# 16_-_POWERS_5V_3V3.net
KiCad netlist of a schematic drawn in Altium Designer
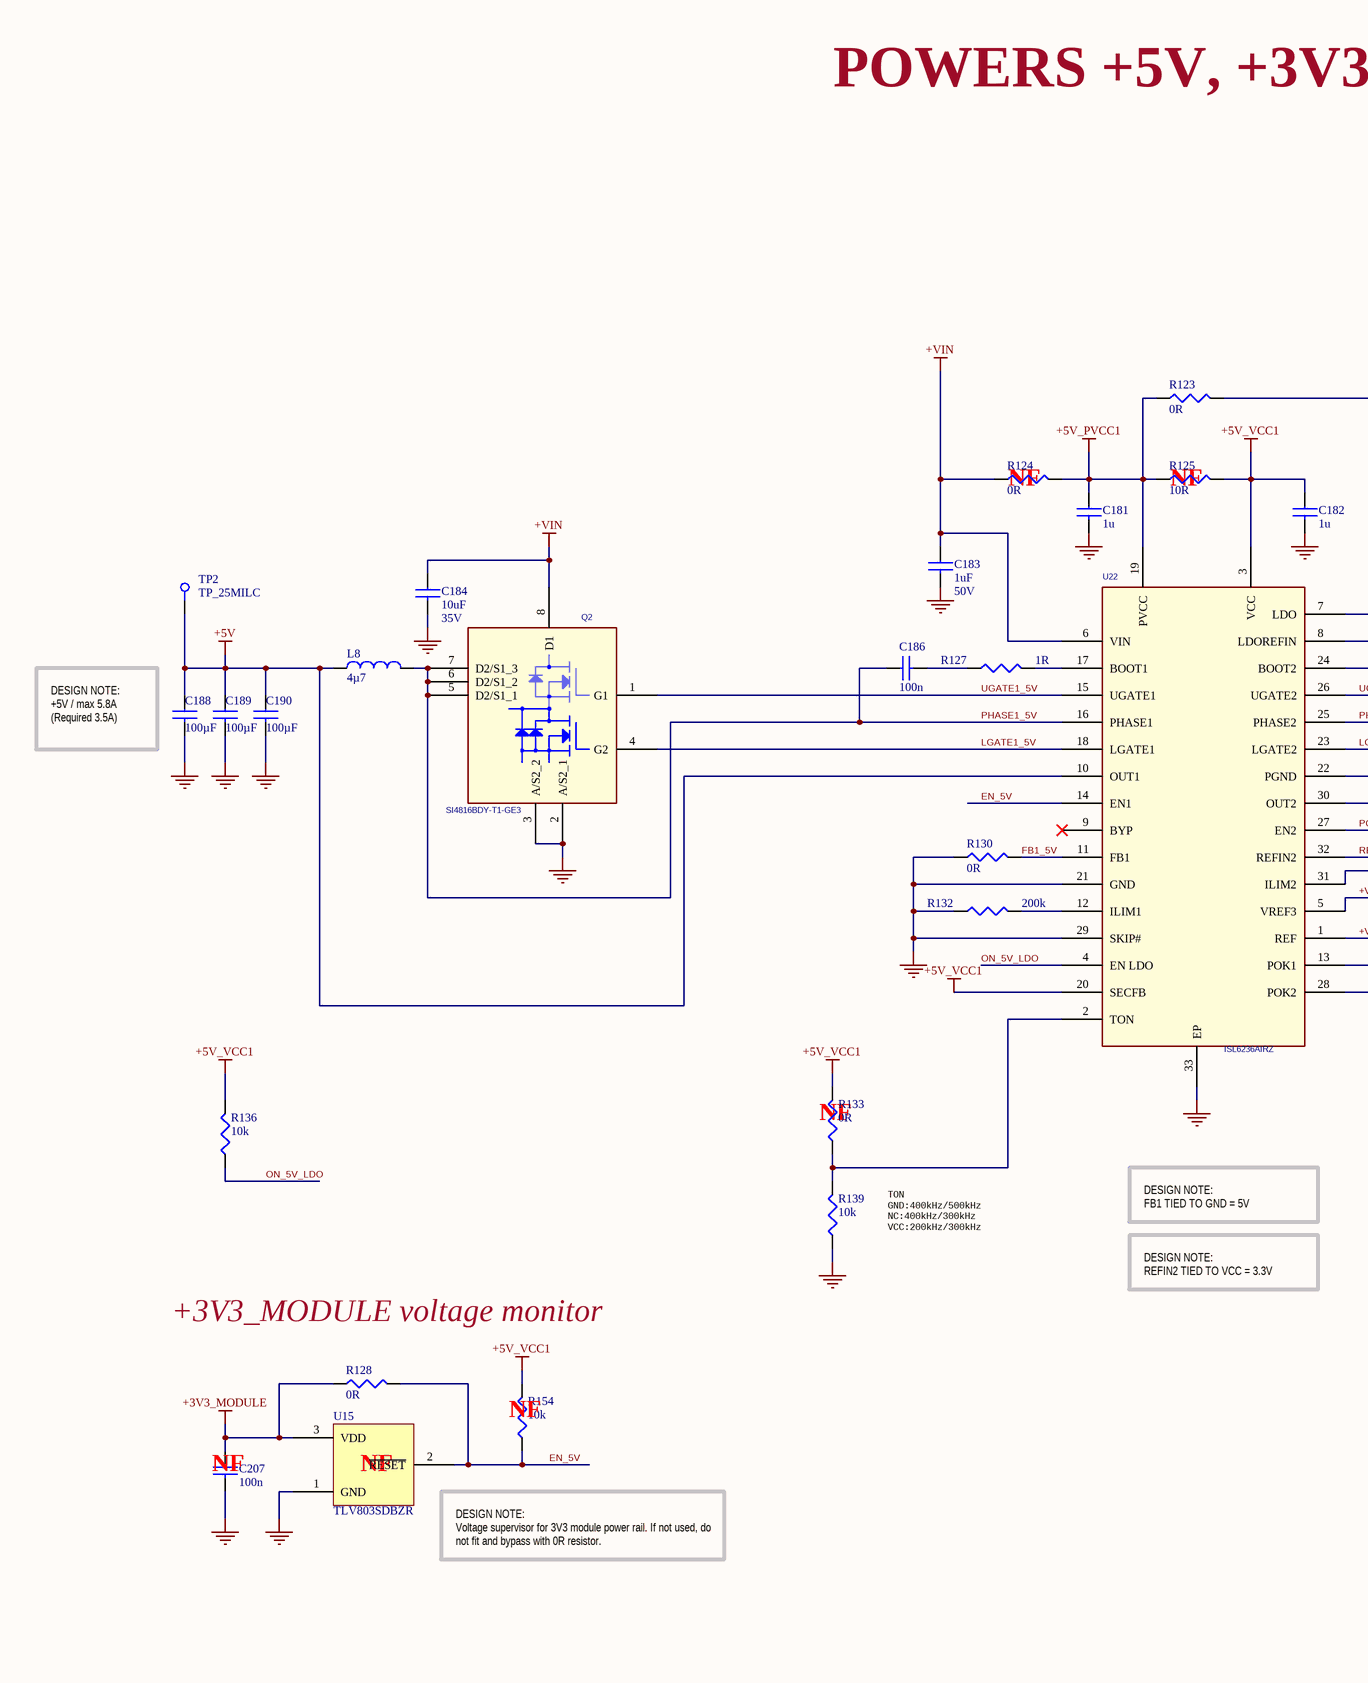
[diagram p0: [16] - POWERS 5V, 3V3.SchDoc, left]
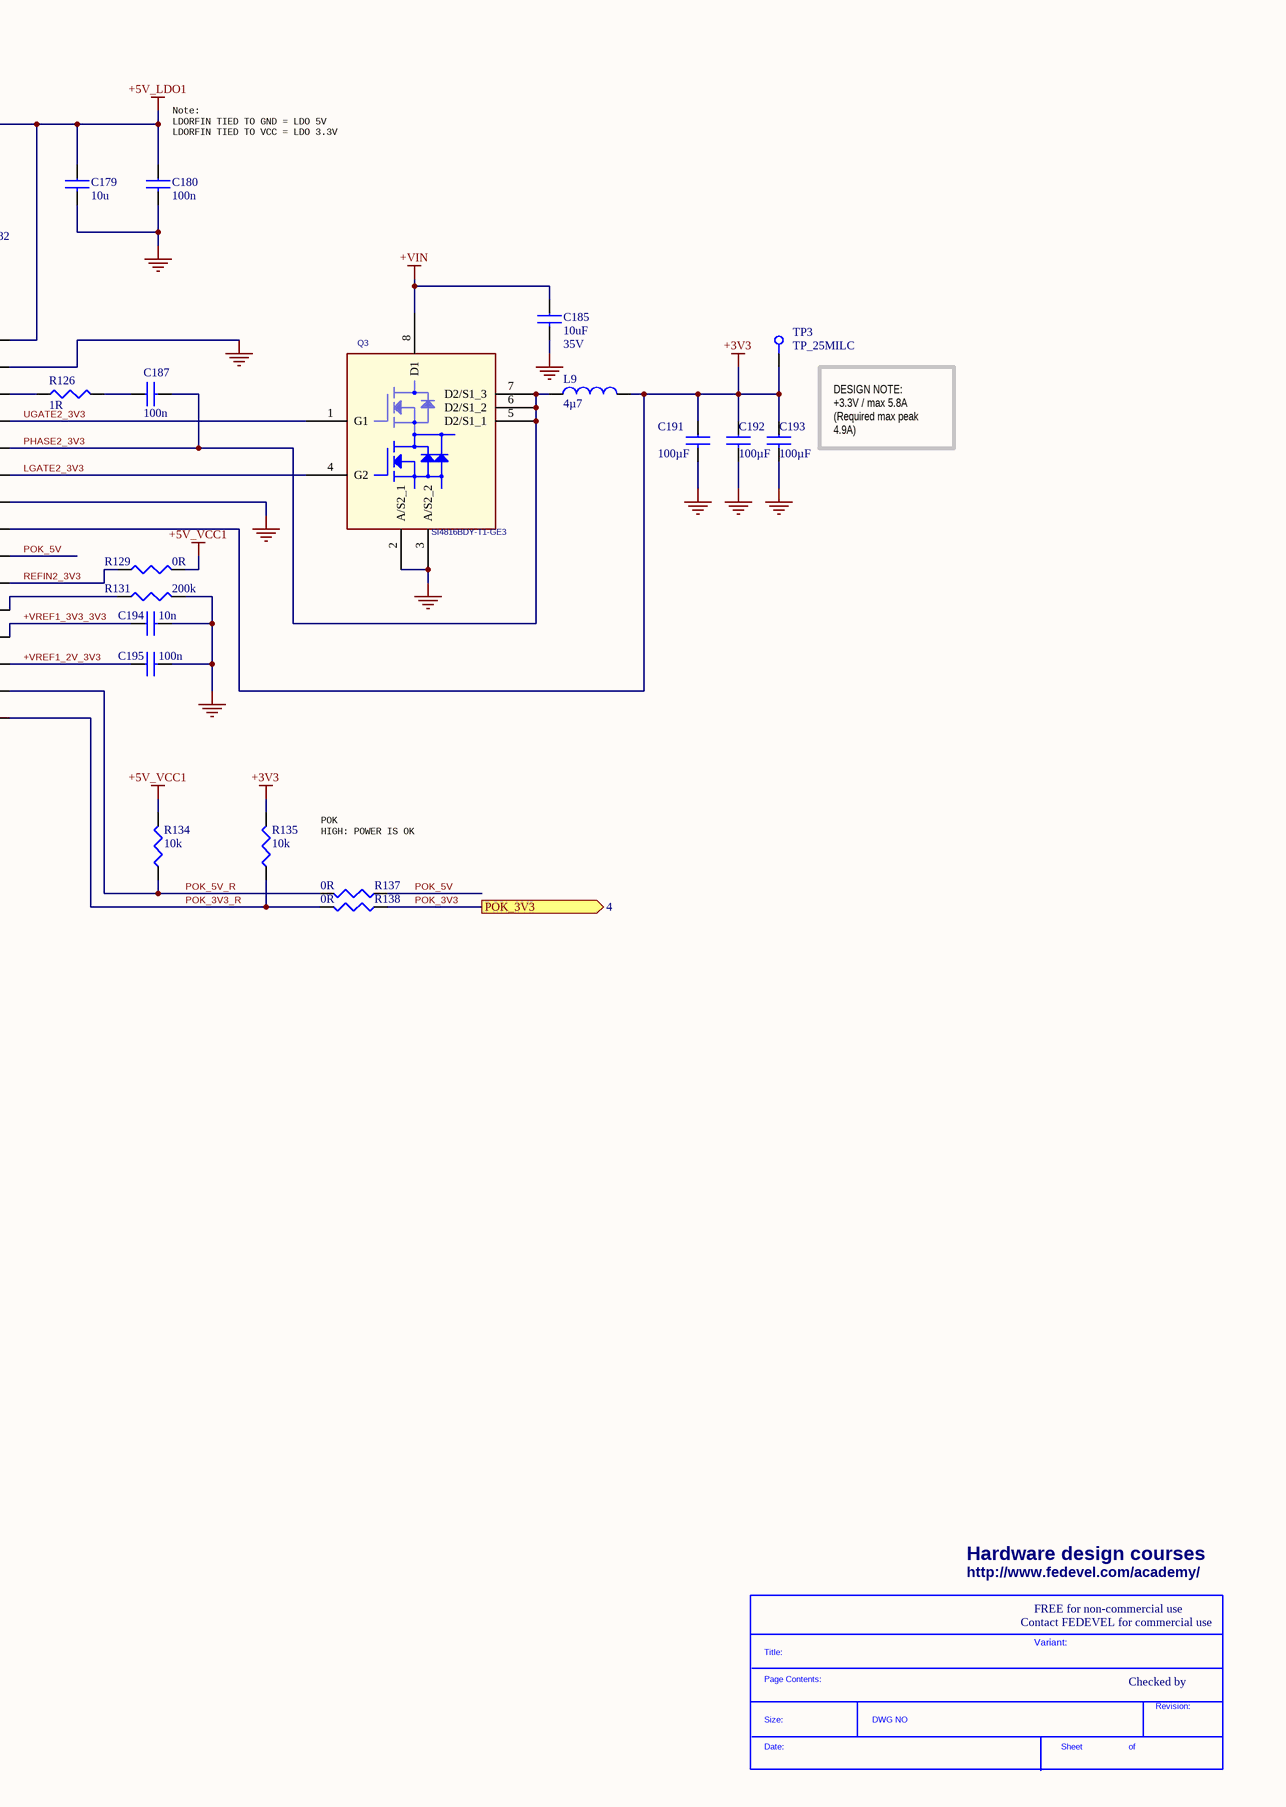
[diagram p1: [16] - POWERS 5V, 3V3.SchDoc, right]

(export (version "E")
  (design (tool "Eeschema 10.0.6"))
  (components
    (comp (ref "C179")
      (value "10u")
      (footprint "C0603")
      (description "CAP CER 10UF 6.3V X5R 20% 0603")
      (fields
        (field (name "MANUFACTURER") "TDK Corporation")
        (field (name "MANUFACTURER PART NUMBER") "C1608X5R0J106M")
      )
      (libsource (lib "Integrated_Library_RF_FEB_2012") (part "C1608X5R0J106M"))
    )
    (comp (ref "C180")
      (value "100n")
      (footprint "C0402")
      (description "CAP CER .10UF 50V X5R 10% 0402")
      (fields
        (field (name "MANUFACTURER") "TDK Corporation")
        (field (name "MANUFACTURER PART NUMBER") "C1005X5R1H104K")
      )
      (libsource (lib "Integrated_Library_RF_FEB_2012") (part "C1005X5R1H104K"))
    )
    (comp (ref "C181")
      (value "1u")
      (footprint "C0402")
      (description "CAP CER 1.0UF 16V X5R 0402")
      (fields
        (field (name "MANUFACTURER") "TDK Corporation")
        (field (name "MANUFACTURER PART NUMBER") "C1005X5R1C105K")
      )
      (libsource (lib "Integrated_Library_RF_FEB_2012") (part "C1005X5R1C105K"))
    )
    (comp (ref "C182")
      (value "1u")
      (footprint "C0402")
      (description "CAP CER 1.0UF 16V X5R 0402")
      (fields
        (field (name "MANUFACTURER") "TDK Corporation")
        (field (name "MANUFACTURER PART NUMBER") "C1005X5R1C105K")
      )
      (libsource (lib "Integrated_Library_RF_FEB_2012") (part "C1005X5R1C105K"))
    )
    (comp (ref "C183")
      (value "1uF")
      (footprint "C0805")
      (description "CAP CER 1UF 50V X7R 0805")
      (fields
        (field (name "MANUFACTURER") "Murata Electronics North America")
        (field (name "MANUFACTURER PART NUMBER") "GRM21BR71H105KA12L")
        (field (name "VOLTAGE - RATED") "50V")
      )
      (libsource (lib "Integrated_Library_RF_FEB_2012") (part "GRM21BR71H105KA12L"))
    )
    (comp (ref "C184")
      (value "10uF")
      (footprint "C1206")
      (description "CAP CER 10UF 35V X5R 1206")
      (fields
        (field (name "MANUFACTURER") "Murata Electronics North America")
        (field (name "MANUFACTURER PART NUMBER") "GRM31CR6YA106KA12L")
        (field (name "VOLTAGE - RATED") "35V")
      )
      (libsource (lib "Integrated_Library_RF_FEB_2012") (part "GRM31CR6YA106KA12L"))
    )
    (comp (ref "C185")
      (value "10uF")
      (footprint "C1206")
      (description "CAP CER 10UF 35V X5R 1206")
      (fields
        (field (name "MANUFACTURER") "Murata Electronics North America")
        (field (name "MANUFACTURER PART NUMBER") "GRM31CR6YA106KA12L")
        (field (name "VOLTAGE - RATED") "35V")
      )
      (libsource (lib "Integrated_Library_RF_FEB_2012") (part "GRM31CR6YA106KA12L"))
    )
    (comp (ref "C186")
      (value "100n")
      (footprint "C0402")
      (description "CAP CER .10UF 50V X5R 10% 0402")
      (fields
        (field (name "MANUFACTURER") "TDK Corporation")
        (field (name "MANUFACTURER PART NUMBER") "C1005X5R1H104K")
      )
      (libsource (lib "Integrated_Library_RF_FEB_2012") (part "C1005X5R1H104K"))
    )
    (comp (ref "C187")
      (value "100n")
      (footprint "C0402")
      (description "CAP CER .10UF 50V X5R 10% 0402")
      (fields
        (field (name "MANUFACTURER") "TDK Corporation")
        (field (name "MANUFACTURER PART NUMBER") "C1005X5R1H104K")
      )
      (libsource (lib "Integrated_Library_RF_FEB_2012") (part "C1005X5R1H104K"))
    )
    (comp (ref "C188")
      (value "100µF")
      (footprint "C1206")
      (description "CAP CER 100UF 10V X5R 20% 1206")
      (fields
        (field (name "MANUFACTURER") "TDK Corporation")
        (field (name "MANUFACTURER PART NUMBER") "C3216X5R1A107M")
      )
      (libsource (lib "Integrated_Library_RF_FEB_2012") (part "C3216X5R1A107M"))
    )
    (comp (ref "C189")
      (value "100µF")
      (footprint "C1206")
      (description "CAP CER 100UF 10V X5R 20% 1206")
      (fields
        (field (name "MANUFACTURER") "TDK Corporation")
        (field (name "MANUFACTURER PART NUMBER") "C3216X5R1A107M")
      )
      (libsource (lib "Integrated_Library_RF_FEB_2012") (part "C3216X5R1A107M"))
    )
    (comp (ref "C190")
      (value "100µF")
      (footprint "C1206")
      (description "CAP CER 100UF 10V X5R 20% 1206")
      (fields
        (field (name "MANUFACTURER") "TDK Corporation")
        (field (name "MANUFACTURER PART NUMBER") "C3216X5R1A107M")
      )
      (libsource (lib "Integrated_Library_RF_FEB_2012") (part "C3216X5R1A107M"))
    )
    (comp (ref "C191")
      (value "100µF")
      (footprint "C1206")
      (description "CAP CER 100UF 10V X5R 20% 1206")
      (fields
        (field (name "MANUFACTURER") "TDK Corporation")
        (field (name "MANUFACTURER PART NUMBER") "C3216X5R1A107M")
      )
      (libsource (lib "Integrated_Library_RF_FEB_2012") (part "C3216X5R1A107M"))
    )
    (comp (ref "C192")
      (value "100µF")
      (footprint "C1206")
      (description "CAP CER 100UF 10V X5R 20% 1206")
      (fields
        (field (name "MANUFACTURER") "TDK Corporation")
        (field (name "MANUFACTURER PART NUMBER") "C3216X5R1A107M")
      )
      (libsource (lib "Integrated_Library_RF_FEB_2012") (part "C3216X5R1A107M"))
    )
    (comp (ref "C193")
      (value "100µF")
      (footprint "C1206")
      (description "CAP CER 100UF 10V X5R 20% 1206")
      (fields
        (field (name "MANUFACTURER") "TDK Corporation")
        (field (name "MANUFACTURER PART NUMBER") "C3216X5R1A107M")
      )
      (libsource (lib "Integrated_Library_RF_FEB_2012") (part "C3216X5R1A107M"))
    )
    (comp (ref "C194")
      (value "10n")
      (footprint "C0402")
      (description "CAP CER 10000PF 16V X7R 10% 0402")
      (fields
        (field (name "MANUFACTURER") "TDK Corporation")
        (field (name "MANUFACTURER PART NUMBER") "C1005X7R1C103K")
      )
      (libsource (lib "Integrated_Library_RF_FEB_2012") (part "C1005X7R1C103K"))
    )
    (comp (ref "C195")
      (value "100n")
      (footprint "C0402")
      (description "CAP CER .10UF 50V X5R 10% 0402")
      (fields
        (field (name "MANUFACTURER") "TDK Corporation")
        (field (name "MANUFACTURER PART NUMBER") "C1005X5R1H104K")
      )
      (libsource (lib "Integrated_Library_RF_FEB_2012") (part "C1005X5R1H104K"))
    )
    (comp (ref "C207")
      (value "100n")
      (footprint "C0402")
      (description "CAP CER .10UF 50V X5R 10% 0402")
      (fields
        (field (name "MANUFACTURER") "TDK Corporation")
        (field (name "MANUFACTURER PART NUMBER") "C1005X5R1H104K")
      )
      (libsource (lib "Integrated_Library_RF_FEB_2012") (part "C1005X5R1H104K"))
    )
    (comp (ref "L8")
      (value "4µ7")
      (footprint "IHLP_255MILx270MIL")
      (description "INDUCTOR POWER 4.7UH 5.5A SMD")
      (fields
        (field (name "MANUFACTURER") "Vishay/Dale")
        (field (name "MANUFACTURER PART NUMBER") "IHLP2525CZER4R7M01")
      )
      (libsource (lib "Integrated_Library_RF_FEB_2012") (part "IHLP2525CZER4R7M01"))
    )
    (comp (ref "L9")
      (value "4µ7")
      (footprint "IHLP_255MILx270MIL")
      (description "INDUCTOR POWER 4.7UH 5.5A SMD")
      (fields
        (field (name "MANUFACTURER") "Vishay/Dale")
        (field (name "MANUFACTURER PART NUMBER") "IHLP2525CZER4R7M01")
      )
      (libsource (lib "Integrated_Library_RF_FEB_2012") (part "IHLP2525CZER4R7M01"))
    )
    (comp (ref "Q2")
      (value "SI4816BDY-T1-GE3")
      (footprint "8_SOIC_3.9MM")
      (description "MOSFET DL N-CH 30V 6.8A 8-SOIC")
      (fields (field (name "MANUFACTURER") "Vishay/Siliconix"))
      (libsource (lib "Integrated_Library_RF_FEB_2012") (part "SI4816BDY-T1-GE3"))
    )
    (comp (ref "Q3")
      (value "SI4816BDY-T1-GE3")
      (footprint "8_SOIC_3.9MM")
      (description "MOSFET DL N-CH 30V 6.8A 8-SOIC")
      (fields (field (name "MANUFACTURER") "Vishay/Siliconix"))
      (libsource (lib "Integrated_Library_RF_FEB_2012") (part "SI4816BDY-T1-GE3"))
    )
    (comp (ref "R123")
      (value "0R")
      (footprint "R0402")
      (description "RES 0.0 OHM 1/16W 0402 SMD")
      (fields
        (field (name "MANUFACTURER") "Yageo")
        (field (name "MANUFACTURER PART NUMBER") "RC0402JR-070RL")
      )
      (libsource (lib "Integrated_Library_RF_FEB_2012") (part "RC0402JR-070RL"))
    )
    (comp (ref "R124")
      (value "0R")
      (footprint "R0402")
      (description "RES 0.0 OHM 1/16W 0402 SMD")
      (fields
        (field (name "MANUFACTURER") "Yageo")
        (field (name "MANUFACTURER PART NUMBER") "RC0402JR-070RL")
      )
      (libsource (lib "Integrated_Library_RF_FEB_2012") (part "RC0402JR-070RL"))
    )
    (comp (ref "R125")
      (value "10R")
      (footprint "R0402")
      (description "RES 10.0 OHM 1/16W 1% 0402 SMD")
      (fields
        (field (name "MANUFACTURER") "Yageo")
        (field (name "MANUFACTURER PART NUMBER") "RC0402FR-0710RL")
      )
      (libsource (lib "Integrated_Library_RF_FEB_2012") (part "RC0402FR-0710RL"))
    )
    (comp (ref "R126")
      (value "1R")
      (footprint "R0402")
      (description "RES 1.00 OHM 1/16W 1% 0402 SM")
      (fields
        (field (name "MANUFACTURER") "Yageo")
        (field (name "MANUFACTURER PART NUMBER") "RC0402FR-071RL")
      )
      (libsource (lib "Integrated_Library_RF_FEB_2012") (part "RC0402FR-071RL"))
    )
    (comp (ref "R127")
      (value "1R")
      (footprint "R0402")
      (description "RES 1.00 OHM 1/16W 1% 0402 SM")
      (fields
        (field (name "MANUFACTURER") "Yageo")
        (field (name "MANUFACTURER PART NUMBER") "RC0402FR-071RL")
      )
      (libsource (lib "Integrated_Library_RF_FEB_2012") (part "RC0402FR-071RL"))
    )
    (comp (ref "R128")
      (value "0R")
      (footprint "R0402")
      (description "RES 0.0 OHM 1/16W 0402 SMD")
      (fields
        (field (name "MANUFACTURER") "Yageo")
        (field (name "MANUFACTURER PART NUMBER") "RC0402JR-070RL")
      )
      (libsource (lib "Integrated_Library_RF_FEB_2012") (part "RC0402JR-070RL"))
    )
    (comp (ref "R129")
      (value "0R")
      (footprint "R0402")
      (description "RES 0.0 OHM 1/16W 0402 SMD")
      (fields
        (field (name "MANUFACTURER") "Yageo")
        (field (name "MANUFACTURER PART NUMBER") "RC0402JR-070RL")
      )
      (libsource (lib "Integrated_Library_RF_FEB_2012") (part "RC0402JR-070RL"))
    )
    (comp (ref "R130")
      (value "0R")
      (footprint "R0402")
      (description "RES 0.0 OHM 1/16W 0402 SMD")
      (fields
        (field (name "MANUFACTURER") "Yageo")
        (field (name "MANUFACTURER PART NUMBER") "RC0402JR-070RL")
      )
      (libsource (lib "Integrated_Library_RF_FEB_2012") (part "RC0402JR-070RL"))
    )
    (comp (ref "R131")
      (value "200k")
      (footprint "R0402")
      (description "RES 200K OHM 1/16W 1% 0402 SMD")
      (fields
        (field (name "MANUFACTURER") "Yageo")
        (field (name "MANUFACTURER PART NUMBER") "RC0402FR-07200KL")
      )
      (libsource (lib "Integrated_Library_RF_FEB_2012") (part "RC0402FR-07200KL"))
    )
    (comp (ref "R132")
      (value "200k")
      (footprint "R0402")
      (description "RES 200K OHM 1/16W 1% 0402 SMD")
      (fields
        (field (name "MANUFACTURER") "Yageo")
        (field (name "MANUFACTURER PART NUMBER") "RC0402FR-07200KL")
      )
      (libsource (lib "Integrated_Library_RF_FEB_2012") (part "RC0402FR-07200KL"))
    )
    (comp (ref "R133")
      (value "0R")
      (footprint "R0402")
      (description "RES 0.0 OHM 1/16W 0402 SMD")
      (fields
        (field (name "MANUFACTURER") "Yageo")
        (field (name "MANUFACTURER PART NUMBER") "RC0402JR-070RL")
      )
      (libsource (lib "Integrated_Library_RF_FEB_2012") (part "RC0402JR-070RL"))
    )
    (comp (ref "R134")
      (value "10k")
      (footprint "R0402")
      (description "RES 10.0K OHM 1/16W 1% 0402 SMD")
      (fields
        (field (name "MANUFACTURER") "Yageo")
        (field (name "MANUFACTURER PART NUMBER") "RC0402FR-0710KL")
      )
      (libsource (lib "Integrated_Library_RF_FEB_2012") (part "RC0402FR-0710KL"))
    )
    (comp (ref "R135")
      (value "10k")
      (footprint "R0402")
      (description "RES 10.0K OHM 1/16W 1% 0402 SMD")
      (fields
        (field (name "MANUFACTURER") "Yageo")
        (field (name "MANUFACTURER PART NUMBER") "RC0402FR-0710KL")
      )
      (libsource (lib "Integrated_Library_RF_FEB_2012") (part "RC0402FR-0710KL"))
    )
    (comp (ref "R136")
      (value "10k")
      (footprint "R0402")
      (description "RES 10.0K OHM 1/16W 1% 0402 SMD")
      (fields
        (field (name "MANUFACTURER") "Yageo")
        (field (name "MANUFACTURER PART NUMBER") "RC0402FR-0710KL")
      )
      (libsource (lib "Integrated_Library_RF_FEB_2012") (part "RC0402FR-0710KL"))
    )
    (comp (ref "R137")
      (value "0R")
      (footprint "R0402")
      (description "RES 0.0 OHM 1/16W 0402 SMD")
      (fields
        (field (name "MANUFACTURER") "Yageo")
        (field (name "MANUFACTURER PART NUMBER") "RC0402JR-070RL")
      )
      (libsource (lib "Integrated_Library_RF_FEB_2012") (part "RC0402JR-070RL"))
    )
    (comp (ref "R138")
      (value "0R")
      (footprint "R0402")
      (description "RES 0.0 OHM 1/16W 0402 SMD")
      (fields
        (field (name "MANUFACTURER") "Yageo")
        (field (name "MANUFACTURER PART NUMBER") "RC0402JR-070RL")
      )
      (libsource (lib "Integrated_Library_RF_FEB_2012") (part "RC0402JR-070RL"))
    )
    (comp (ref "R139")
      (value "10k")
      (footprint "R0402")
      (description "RES 10.0K OHM 1/16W 1% 0402 SMD")
      (fields
        (field (name "MANUFACTURER") "Yageo")
        (field (name "MANUFACTURER PART NUMBER") "RC0402FR-0710KL")
      )
      (libsource (lib "Integrated_Library_RF_FEB_2012") (part "RC0402FR-0710KL"))
    )
    (comp (ref "R154")
      (value "10k")
      (footprint "R0402")
      (description "RES 10.0K OHM 1/16W 1% 0402 SMD")
      (fields
        (field (name "MANUFACTURER") "Yageo")
        (field (name "MANUFACTURER PART NUMBER") "RC0402FR-0710KL")
      )
      (libsource (lib "Integrated_Library_RF_FEB_2012") (part "RC0402FR-0710KL"))
    )
    (comp (ref "TP2")
      (value "TP_25MILC")
      (footprint "TP_25C")
      (description "Test Point 25mil")
      (libsource (lib "Integrated_Library_RF_FEB_2012") (part "TP_25MILC"))
    )
    (comp (ref "TP3")
      (value "TP_25MILC")
      (footprint "TP_25C")
      (description "Test Point 25mil")
      (libsource (lib "Integrated_Library_RF_FEB_2012") (part "TP_25MILC"))
    )
    (comp (ref "U15")
      (value "TLV803SDBZR")
      (footprint "DBZ")
      (description "IC VOLT SUPERVISR 2.93V SOT23-3")
      (fields
        (field (name "MANUFACTURER") "Texas Instruments")
        (field (name ".CREATOR") "MM")
        (field (name ".CHECKED PCB") "MM")
        (field (name ".CHECKED SCH") "MM")
      )
      (libsource (lib "Integrated_Library_RF_FEB_2012") (part "TLV803SDBZR"))
    )
    (comp (ref "U22")
      (value "ISL6236AIRZ")
      (footprint "32_VFQFN_EXPOSED_PAD")
      (description "IC MAIN PWR CTRLR QUAD 32-QFN")
      (fields (field (name "MANUFACTURER") "Intersil"))
      (libsource (lib "Integrated_Library_RF_FEB_2012") (part "ISL6236AIRZ"))
    )
  )
  (nets
    (net (code "1") (name "+3V3") (class "Default")
      (node (ref "C191") (pin "1") (pinfunction "1_1") (pintype "passive"))
      (node (ref "C192") (pin "1") (pinfunction "1_1") (pintype "passive"))
      (node (ref "C193") (pin "1") (pinfunction "1_1") (pintype "passive"))
      (node (ref "L9") (pin "2") (pinfunction "2_2") (pintype "passive"))
      (node (ref "R135") (pin "2") (pinfunction "2_2") (pintype "passive"))
      (node (ref "TP3") (pin "1") (pinfunction "1_1") (pintype "passive"))
      (node (ref "U22") (pin "30") (pinfunction "OUT2_30") (pintype "passive"))
    )
    (net (code "2") (name "+3V3_MODULE") (class "Default")
      (node (ref "C207") (pin "1") (pinfunction "1_1") (pintype "passive"))
      (node (ref "R128") (pin "1") (pinfunction "1_1") (pintype "passive"))
      (node (ref "U15") (pin "3") (pinfunction "VDD_3") (pintype "passive"))
    )
    (net (code "3") (name "+5V") (class "Default")
      (node (ref "C188") (pin "1") (pinfunction "1_1") (pintype "passive"))
      (node (ref "C189") (pin "1") (pinfunction "1_1") (pintype "passive"))
      (node (ref "C190") (pin "1") (pinfunction "1_1") (pintype "passive"))
      (node (ref "L8") (pin "1") (pinfunction "1_1") (pintype "passive"))
      (node (ref "TP2") (pin "1") (pinfunction "1_1") (pintype "passive"))
      (node (ref "U22") (pin "10") (pinfunction "OUT1_10") (pintype "passive"))
    )
    (net (code "4") (name "+5V_LDO1") (class "Default")
      (node (ref "C179") (pin "1") (pinfunction "1_1") (pintype "passive"))
      (node (ref "C180") (pin "1") (pinfunction "1_1") (pintype "passive"))
      (node (ref "R123") (pin "2") (pinfunction "2_2") (pintype "passive"))
      (node (ref "U22") (pin "7") (pinfunction "LDO_7") (pintype "passive"))
    )
    (net (code "5") (name "+5V_PVCC1") (class "Default")
      (node (ref "C181") (pin "1") (pinfunction "1_1") (pintype "passive"))
      (node (ref "R123") (pin "1") (pinfunction "1_1") (pintype "passive"))
      (node (ref "R124") (pin "2") (pinfunction "2_2") (pintype "passive"))
      (node (ref "R125") (pin "1") (pinfunction "1_1") (pintype "passive"))
      (node (ref "U22") (pin "19") (pinfunction "PVCC_19") (pintype "passive"))
    )
    (net (code "6") (name "+5V_VCC1") (class "Default")
      (node (ref "C182") (pin "1") (pinfunction "1_1") (pintype "passive"))
      (node (ref "R125") (pin "2") (pinfunction "2_2") (pintype "passive"))
      (node (ref "R129") (pin "2") (pinfunction "2_2") (pintype "passive"))
      (node (ref "R133") (pin "2") (pinfunction "2_2") (pintype "passive"))
      (node (ref "R134") (pin "2") (pinfunction "2_2") (pintype "passive"))
      (node (ref "R136") (pin "2") (pinfunction "2_2") (pintype "passive"))
      (node (ref "R154") (pin "2") (pinfunction "2_2") (pintype "passive"))
      (node (ref "U22") (pin "20") (pinfunction "SECFB_20") (pintype "passive"))
      (node (ref "U22") (pin "3") (pinfunction "VCC_3") (pintype "passive"))
    )
    (net (code "7") (name "+VIN") (class "Default")
      (node (ref "C183") (pin "1") (pinfunction "1_1") (pintype "passive"))
      (node (ref "C184") (pin "1") (pinfunction "1_1") (pintype "passive"))
      (node (ref "C185") (pin "1") (pinfunction "1_1") (pintype "passive"))
      (node (ref "Q2") (pin "8") (pinfunction "D1_8") (pintype "passive"))
      (node (ref "Q3") (pin "8") (pinfunction "D1_8") (pintype "passive"))
      (node (ref "R124") (pin "1") (pinfunction "1_1") (pintype "passive"))
      (node (ref "U22") (pin "6") (pinfunction "VIN_6") (pintype "passive"))
    )
    (net (code "8") (name "/+VREF1_2V_3V3") (class "Default")
      (node (ref "C195") (pin "1") (pinfunction "1_1") (pintype "passive"))
      (node (ref "U22") (pin "1") (pinfunction "REF_1") (pintype "passive"))
    )
    (net (code "9") (name "/+VREF1_3V3_3V3") (class "Default")
      (node (ref "C194") (pin "1") (pinfunction "1_1") (pintype "passive"))
      (node (ref "U22") (pin "5") (pinfunction "VREF3_5") (pintype "passive"))
    )
    (net (code "10") (name "/EN_5V") (class "Default")
      (node (ref "R128") (pin "2") (pinfunction "2_2") (pintype "passive"))
      (node (ref "R154") (pin "1") (pinfunction "1_1") (pintype "passive"))
      (node (ref "U15") (pin "2") (pinfunction "~{RESET}_2") (pintype "passive"))
      (node (ref "U22") (pin "14") (pinfunction "EN1_14") (pintype "passive"))
    )
    (net (code "11") (name "/FB1_5V") (class "Default")
      (node (ref "R130") (pin "2") (pinfunction "2_2") (pintype "passive"))
      (node (ref "U22") (pin "11") (pinfunction "FB1_11") (pintype "passive"))
    )
    (net (code "12") (name "/LGATE1_5V") (class "Default")
      (node (ref "Q2") (pin "4") (pinfunction "G2_4") (pintype "passive"))
      (node (ref "U22") (pin "18") (pinfunction "LGATE1_18") (pintype "passive"))
    )
    (net (code "13") (name "/LGATE2_3V3") (class "Default")
      (node (ref "Q3") (pin "4") (pinfunction "G2_4") (pintype "passive"))
      (node (ref "U22") (pin "23") (pinfunction "LGATE2_23") (pintype "passive"))
    )
    (net (code "14") (name "/ON_5V_LDO") (class "Default")
      (node (ref "R136") (pin "1") (pinfunction "1_1") (pintype "passive"))
      (node (ref "U22") (pin "4") (pinfunction "EN_LDO_4") (pintype "passive"))
    )
    (net (code "15") (name "/PHASE1_5V") (class "Default")
      (node (ref "C186") (pin "1") (pinfunction "1_1") (pintype "passive"))
      (node (ref "L8") (pin "2") (pinfunction "2_2") (pintype "passive"))
      (node (ref "Q2") (pin "5") (pinfunction "D2/S1_1_5") (pintype "passive"))
      (node (ref "Q2") (pin "6") (pinfunction "D2/S1_2_6") (pintype "passive"))
      (node (ref "Q2") (pin "7") (pinfunction "D2/S1_3_7") (pintype "passive"))
      (node (ref "U22") (pin "16") (pinfunction "PHASE1_16") (pintype "passive"))
    )
    (net (code "16") (name "/PHASE2_3V3") (class "Default")
      (node (ref "C187") (pin "2") (pinfunction "2_2") (pintype "passive"))
      (node (ref "L9") (pin "1") (pinfunction "1_1") (pintype "passive"))
      (node (ref "Q3") (pin "5") (pinfunction "D2/S1_1_5") (pintype "passive"))
      (node (ref "Q3") (pin "6") (pinfunction "D2/S1_2_6") (pintype "passive"))
      (node (ref "Q3") (pin "7") (pinfunction "D2/S1_3_7") (pintype "passive"))
      (node (ref "U22") (pin "25") (pinfunction "PHASE2_25") (pintype "passive"))
    )
    (net (code "17") (name "/POK_3V3") (class "Default")
      (node (ref "R138") (pin "1") (pinfunction "1_1") (pintype "passive"))
    )
    (net (code "18") (name "/POK_3V3_R") (class "Default")
      (node (ref "R135") (pin "1") (pinfunction "1_1") (pintype "passive"))
      (node (ref "R138") (pin "2") (pinfunction "2_2") (pintype "passive"))
      (node (ref "U22") (pin "28") (pinfunction "POK2_28") (pintype "passive"))
    )
    (net (code "19") (name "/POK_5V") (class "Default")
      (node (ref "R137") (pin "1") (pinfunction "1_1") (pintype "passive"))
      (node (ref "U22") (pin "27") (pinfunction "EN2_27") (pintype "passive"))
    )
    (net (code "20") (name "/POK_5V_R") (class "Default")
      (node (ref "R134") (pin "1") (pinfunction "1_1") (pintype "passive"))
      (node (ref "R137") (pin "2") (pinfunction "2_2") (pintype "passive"))
      (node (ref "U22") (pin "13") (pinfunction "POK1_13") (pintype "passive"))
    )
    (net (code "21") (name "/REFIN2_3V3") (class "Default")
      (node (ref "R129") (pin "1") (pinfunction "1_1") (pintype "passive"))
      (node (ref "U22") (pin "32") (pinfunction "REFIN2_32") (pintype "passive"))
    )
    (net (code "22") (name "/UGATE1_5V") (class "Default")
      (node (ref "Q2") (pin "1") (pinfunction "G1_1") (pintype "passive"))
      (node (ref "U22") (pin "15") (pinfunction "UGATE1_15") (pintype "passive"))
    )
    (net (code "23") (name "/UGATE2_3V3") (class "Default")
      (node (ref "Q3") (pin "1") (pinfunction "G1_1") (pintype "passive"))
      (node (ref "U22") (pin "26") (pinfunction "UGATE2_26") (pintype "passive"))
    )
    (net (code "24") (name "GND") (class "Default")
      (node (ref "C179") (pin "2") (pinfunction "2_2") (pintype "passive"))
      (node (ref "C180") (pin "2") (pinfunction "2_2") (pintype "passive"))
      (node (ref "C181") (pin "2") (pinfunction "2_2") (pintype "passive"))
      (node (ref "C182") (pin "2") (pinfunction "2_2") (pintype "passive"))
      (node (ref "C183") (pin "2") (pinfunction "2_2") (pintype "passive"))
      (node (ref "C184") (pin "2") (pinfunction "2_2") (pintype "passive"))
      (node (ref "C185") (pin "2") (pinfunction "2_2") (pintype "passive"))
      (node (ref "C188") (pin "2") (pinfunction "2_2") (pintype "passive"))
      (node (ref "C189") (pin "2") (pinfunction "2_2") (pintype "passive"))
      (node (ref "C190") (pin "2") (pinfunction "2_2") (pintype "passive"))
      (node (ref "C191") (pin "2") (pinfunction "2_2") (pintype "passive"))
      (node (ref "C192") (pin "2") (pinfunction "2_2") (pintype "passive"))
      (node (ref "C193") (pin "2") (pinfunction "2_2") (pintype "passive"))
      (node (ref "C194") (pin "2") (pinfunction "2_2") (pintype "passive"))
      (node (ref "C195") (pin "2") (pinfunction "2_2") (pintype "passive"))
      (node (ref "C207") (pin "2") (pinfunction "2_2") (pintype "passive"))
      (node (ref "Q2") (pin "2") (pinfunction "A/S2_1_2") (pintype "passive"))
      (node (ref "Q2") (pin "3") (pinfunction "A/S2_2_3") (pintype "passive"))
      (node (ref "Q3") (pin "2") (pinfunction "A/S2_1_2") (pintype "passive"))
      (node (ref "Q3") (pin "3") (pinfunction "A/S2_2_3") (pintype "passive"))
      (node (ref "R130") (pin "1") (pinfunction "1_1") (pintype "passive"))
      (node (ref "R131") (pin "2") (pinfunction "2_2") (pintype "passive"))
      (node (ref "R132") (pin "1") (pinfunction "1_1") (pintype "passive"))
      (node (ref "R139") (pin "1") (pinfunction "1_1") (pintype "passive"))
      (node (ref "U15") (pin "1") (pinfunction "GND_1") (pintype "passive"))
      (node (ref "U22") (pin "21") (pinfunction "GND_21") (pintype "passive"))
      (node (ref "U22") (pin "22") (pinfunction "PGND_22") (pintype "passive"))
      (node (ref "U22") (pin "29") (pinfunction "SKIP#_29") (pintype "passive"))
      (node (ref "U22") (pin "33") (pinfunction "EP_33") (pintype "passive"))
      (node (ref "U22") (pin "8") (pinfunction "LDOREFIN_8") (pintype "passive"))
    )
    (net (code "25") (name "Net-(C186-Pad2)") (class "Default")
      (node (ref "C186") (pin "2") (pinfunction "2_2") (pintype "passive"))
      (node (ref "R127") (pin "1") (pinfunction "1_1") (pintype "passive"))
    )
    (net (code "26") (name "Net-(C187-Pad1)") (class "Default")
      (node (ref "C187") (pin "1") (pinfunction "1_1") (pintype "passive"))
      (node (ref "R126") (pin "2") (pinfunction "2_2") (pintype "passive"))
    )
    (net (code "27") (name "Net-(U22-BOOT1)") (class "Default")
      (node (ref "R127") (pin "2") (pinfunction "2_2") (pintype "passive"))
      (node (ref "U22") (pin "17") (pinfunction "BOOT1_17") (pintype "passive"))
    )
    (net (code "28") (name "Net-(U22-BOOT2)") (class "Default")
      (node (ref "R126") (pin "1") (pinfunction "1_1") (pintype "passive"))
      (node (ref "U22") (pin "24") (pinfunction "BOOT2_24") (pintype "passive"))
    )
    (net (code "29") (name "Net-(U22-ILIM1)") (class "Default")
      (node (ref "R132") (pin "2") (pinfunction "2_2") (pintype "passive"))
      (node (ref "U22") (pin "12") (pinfunction "ILIM1_12") (pintype "passive"))
    )
    (net (code "30") (name "Net-(U22-ILIM2)") (class "Default")
      (node (ref "R131") (pin "1") (pinfunction "1_1") (pintype "passive"))
      (node (ref "U22") (pin "31") (pinfunction "ILIM2_31") (pintype "passive"))
    )
    (net (code "31") (name "Net-(U22-TON)") (class "Default")
      (node (ref "R133") (pin "1") (pinfunction "1_1") (pintype "passive"))
      (node (ref "R139") (pin "2") (pinfunction "2_2") (pintype "passive"))
      (node (ref "U22") (pin "2") (pinfunction "TON_2") (pintype "passive"))
    )
    (net (code "32") (name "unconnected-(U22-BYP-Pad9)") (class "Default")
      (node (ref "U22") (pin "9") (pinfunction "BYP_9") (pintype "passive+no_connect"))
    )
  )
)
